# FTDI.net
KiCad netlist of a schematic drawn in Altium Designer
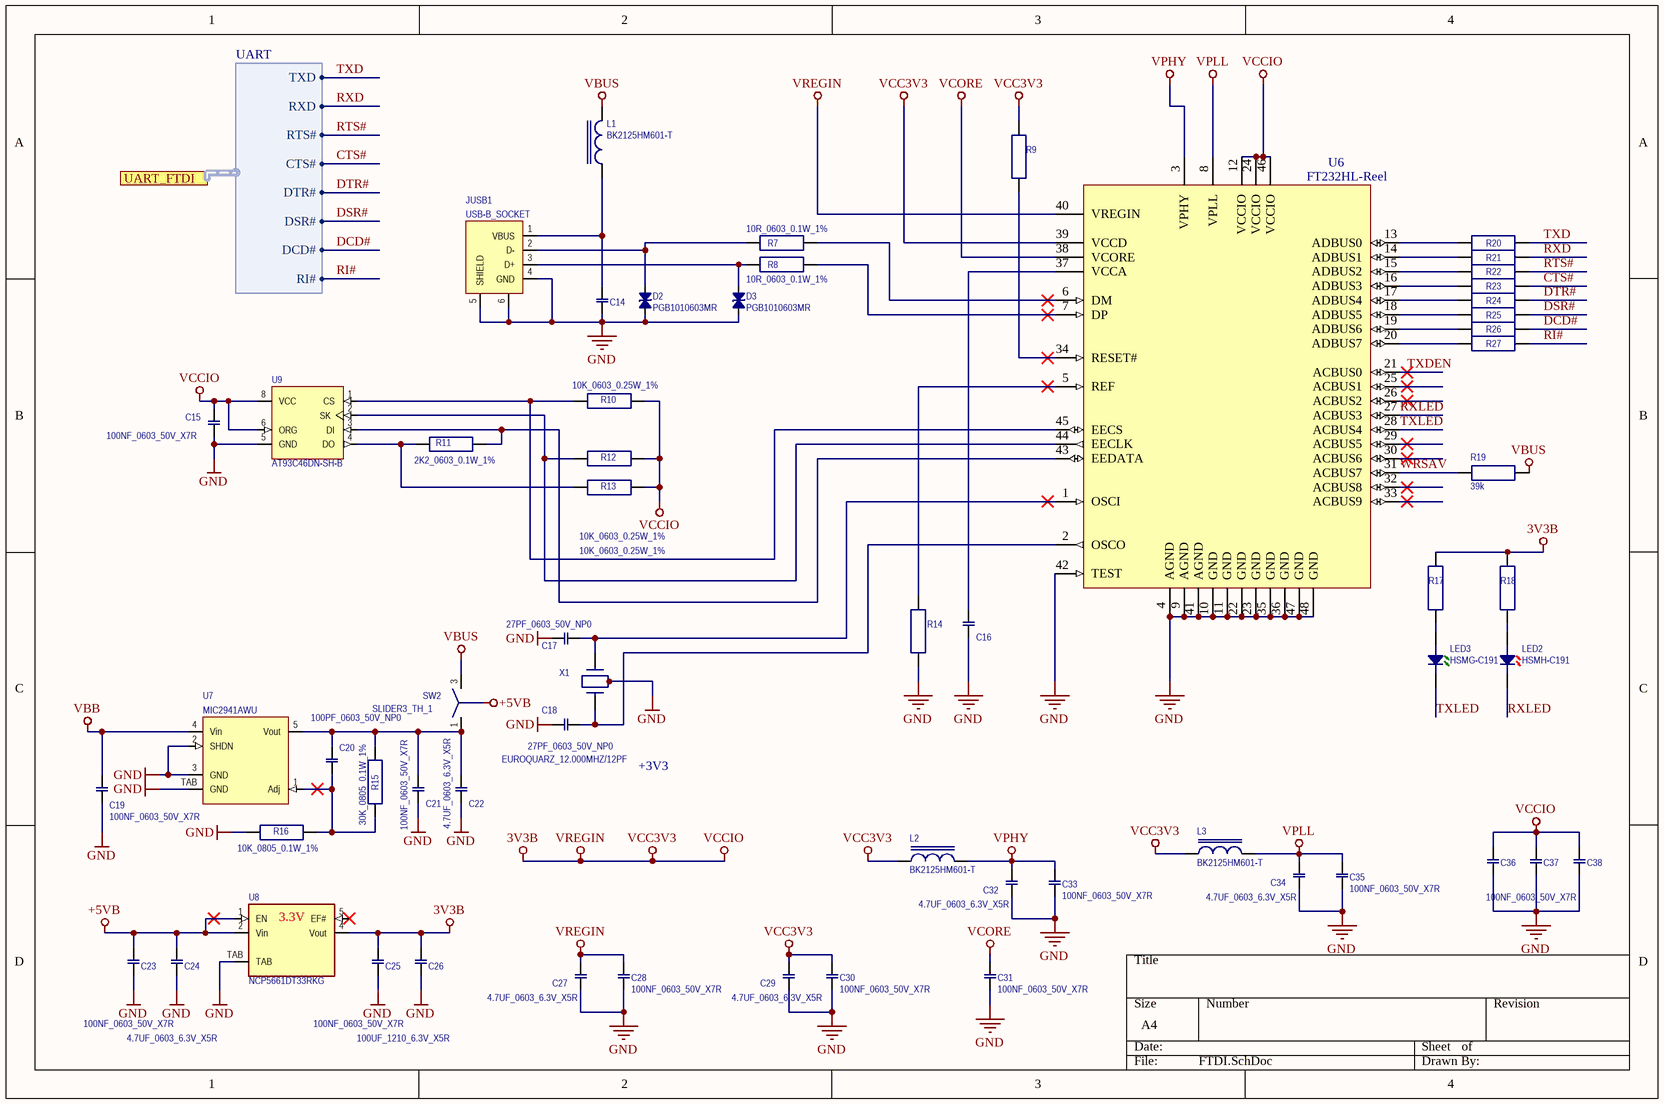
[diagram p0: FTDI.SchDoc]

(export (version "E")
  (design (tool "Eeschema 10.0.6"))
  (components
    (comp (ref "C14")
      (value "10NF_0603_50V_X7R")
      (footprint "CAP0603")
      (description "128-8255    Capacitor MLC-X7R_0603_100NF_10%_50V; C0603C104K5RAC; KEMET; RoHS=Yes")
      (libsource (lib "ONEMULA_V2") (part "100NF_0603_50V_X7R"))
    )
    (comp (ref "C15")
      (value "100NF_0603_50V_X7R")
      (footprint "CAP0603")
      (description "128-8255    Capacitor MLC-X7R_0603_100NF_10%_50V; C0603C104K5RAC; KEMET; RoHS=Yes")
      (libsource (lib "*") (part "100NF_0603_50V_X7R"))
    )
    (comp (ref "C16")
      (value "100NF_0603_50V_X7R")
      (footprint "CAP0603")
      (description "128-8255    Capacitor MLC-X7R_0603_100NF_10%_50V; C0603C104K5RAC; KEMET; RoHS=Yes")
      (libsource (lib "ONEMULA_V2") (part "100NF_0603_50V_X7R"))
    )
    (comp (ref "C17")
      (value "27PF_0603_50V_NP0")
      (footprint "CAP0603")
      (description "141-4627    Capacitor MLC-NPO_0603_27PF_5%_50V; C0603C270J5GAC; KEMET; RoHS=Yes")
      (libsource (lib "*") (part "27PF_0603_50V_NP0"))
    )
    (comp (ref "C18")
      (value "27PF_0603_50V_NP0")
      (footprint "CAP0603")
      (description "141-4627    Capacitor MLC-NPO_0603_27PF_5%_50V; C0603C270J5GAC; KEMET; RoHS=Yes")
      (libsource (lib "*") (part "27PF_0603_50V_NP0"))
    )
    (comp (ref "C19")
      (value "100NF_0603_50V_X7R")
      (footprint "CAP0603")
      (description "128-8255    Capacitor MLC-X7R_0603_100NF_10%_50V; C0603C104K5RAC; KEMET; RoHS=Yes")
      (libsource (lib "*") (part "100NF_0603_50V_X7R"))
    )
    (comp (ref "C20")
      (value "100PF_0603_50V_NP0")
      (footprint "CAP0603")
      (description "141-4603    Capacitor MLC-NPO_0603_100PF_5%_50V; C0603C101J5GAC; KEMET; RoHS=Yes")
      (libsource (lib "*") (part "100PF_0603_50V_NP0"))
    )
    (comp (ref "C21")
      (value "100NF_0603_50V_X7R")
      (footprint "CAP0603")
      (description "128-8255    Capacitor MLC-X7R_0603_100NF_10%_50V; C0603C104K5RAC; KEMET; RoHS=Yes")
      (libsource (lib "*") (part "100NF_0603_50V_X7R"))
    )
    (comp (ref "C22")
      (value "4.7UF_0603_6.3V_X5R")
      (footprint "CAP0603")
      (description "940-2110    Capacitor MLC-X5R_0603_4.7uF_10%_6.3V; 225520613672; PHYCOMP; RoHS=Yes")
      (libsource (lib "*") (part "4.7UF_0603_6.3V_X5R"))
    )
    (comp (ref "C23")
      (value "100NF_0603_50V_X7R")
      (footprint "CAP0603")
      (description "128-8255    Capacitor MLC-X7R_0603_100NF_10%_50V; C0603C104K5RAC; KEMET; RoHS=Yes")
      (libsource (lib "*") (part "100NF_0603_50V_X7R"))
    )
    (comp (ref "C24")
      (value "4.7UF_0603_6.3V_X5R")
      (footprint "CAP0603")
      (description "940-2110    Capacitor MLC-X5R_0603_4.7uF_10%_6.3V; 225520613672; PHYCOMP; RoHS=Yes")
      (libsource (lib "*") (part "4.7UF_0603_6.3V_X5R"))
    )
    (comp (ref "C25")
      (value "100NF_0603_50V_X7R")
      (footprint "CAP0603")
      (description "128-8255    Capacitor MLC-X7R_0603_100NF_10%_50V; C0603C104K5RAC; KEMET; RoHS=Yes")
      (libsource (lib "*") (part "100NF_0603_50V_X7R"))
    )
    (comp (ref "C26")
      (value "100UF_1210_6.3V_X5R")
      (footprint "CAP1210")
      (description "182-8817    Capacitor CML 100uF_1210_6.3V_X5R_20%; GRM32ER60J107ME20L; MURATA; RoHS=Yes")
      (libsource (lib "*") (part "100UF_1210_6.3V_X5R"))
    )
    (comp (ref "C27")
      (value "4.7UF_0603_6.3V_X5R")
      (footprint "CAP0603")
      (description "940-2110    Capacitor MLC-X5R_0603_4.7uF_10%_6.3V; 225520613672; PHYCOMP; RoHS=Yes")
      (libsource (lib "ONEMULA_V2") (part "4.7UF_0603_6.3V_X5R"))
    )
    (comp (ref "C28")
      (value "100NF_0603_50V_X7R")
      (footprint "CAP0603")
      (description "128-8255    Capacitor MLC-X7R_0603_100NF_10%_50V; C0603C104K5RAC; KEMET; RoHS=Yes")
      (libsource (lib "ONEMULA_V2") (part "100NF_0603_50V_X7R"))
    )
    (comp (ref "C29")
      (value "4.7UF_0603_6.3V_X5R")
      (footprint "CAP0603")
      (description "940-2110    Capacitor MLC-X5R_0603_4.7uF_10%_6.3V; 225520613672; PHYCOMP; RoHS=Yes")
      (libsource (lib "ONEMULA_V2") (part "4.7UF_0603_6.3V_X5R"))
    )
    (comp (ref "C30")
      (value "100NF_0603_50V_X7R")
      (footprint "CAP0603")
      (description "128-8255    Capacitor MLC-X7R_0603_100NF_10%_50V; C0603C104K5RAC; KEMET; RoHS=Yes")
      (libsource (lib "ONEMULA_V2") (part "100NF_0603_50V_X7R"))
    )
    (comp (ref "C31")
      (value "100NF_0603_50V_X7R")
      (footprint "CAP0603")
      (description "128-8255    Capacitor MLC-X7R_0603_100NF_10%_50V; C0603C104K5RAC; KEMET; RoHS=Yes")
      (libsource (lib "ONEMULA_V2") (part "100NF_0603_50V_X7R"))
    )
    (comp (ref "C32")
      (value "4.7UF_0603_6.3V_X5R")
      (footprint "CAP0603")
      (description "940-2110    Capacitor MLC-X5R_0603_4.7uF_10%_6.3V; 225520613672; PHYCOMP; RoHS=Yes")
      (libsource (lib "ONEMULA_V2") (part "4.7UF_0603_6.3V_X5R"))
    )
    (comp (ref "C33")
      (value "100NF_0603_50V_X7R")
      (footprint "CAP0603")
      (description "128-8255    Capacitor MLC-X7R_0603_100NF_10%_50V; C0603C104K5RAC; KEMET; RoHS=Yes")
      (libsource (lib "ONEMULA_V2") (part "100NF_0603_50V_X7R"))
    )
    (comp (ref "C34")
      (value "4.7UF_0603_6.3V_X5R")
      (footprint "CAP0603")
      (description "940-2110    Capacitor MLC-X5R_0603_4.7uF_10%_6.3V; 225520613672; PHYCOMP; RoHS=Yes")
      (libsource (lib "ONEMULA_V2") (part "4.7UF_0603_6.3V_X5R"))
    )
    (comp (ref "C35")
      (value "100NF_0603_50V_X7R")
      (footprint "CAP0603")
      (description "128-8255    Capacitor MLC-X7R_0603_100NF_10%_50V; C0603C104K5RAC; KEMET; RoHS=Yes")
      (libsource (lib "ONEMULA_V2") (part "100NF_0603_50V_X7R"))
    )
    (comp (ref "C36")
      (value "100NF_0603_50V_X7R")
      (footprint "CAP0603")
      (description "128-8255    Capacitor MLC-X7R_0603_100NF_10%_50V; C0603C104K5RAC; KEMET; RoHS=Yes")
      (libsource (lib "ONEMULA_V2") (part "100NF_0603_50V_X7R"))
    )
    (comp (ref "C37")
      (value "100NF_0603_50V_X7R")
      (footprint "CAP0603")
      (description "128-8255    Capacitor MLC-X7R_0603_100NF_10%_50V; C0603C104K5RAC; KEMET; RoHS=Yes")
      (libsource (lib "ONEMULA_V2") (part "100NF_0603_50V_X7R"))
    )
    (comp (ref "C38")
      (value "100NF_0603_50V_X7R")
      (footprint "CAP0603")
      (description "128-8255    Capacitor MLC-X7R_0603_100NF_10%_50V; C0603C104K5RAC; KEMET; RoHS=Yes")
      (libsource (lib "ONEMULA_V2") (part "100NF_0603_50V_X7R"))
    )
    (comp (ref "D2")
      (value "PGB1010603MR")
      (footprint "0603")
      (description "175-7240   SUPPRESSOR, ESD, 15KV; PGB1010603MR; LITTELFUSE; RoHS=Yes")
      (libsource (lib "ONEMULA_V2") (part "PGB1010603MR"))
    )
    (comp (ref "D3")
      (value "PGB1010603MR")
      (footprint "0603")
      (description "175-7240   SUPPRESSOR, ESD, 15KV; PGB1010603MR; LITTELFUSE; RoHS=Yes")
      (libsource (lib "ONEMULA_V2") (part "PGB1010603MR"))
    )
    (comp (ref "JUSB1")
      (value "USB-B_SOCKET")
      (footprint "USB-B_SOCKET")
      (description "117-7885    USB PANEL SOCKET PCB TYPE B; 2411 02; LUMBERG; RoHS=Yes")
      (libsource (lib "ONEMULA_V2") (part "USB-B_SOCKET"))
    )
    (comp (ref "L1")
      (value "BK2125HM601-T")
      (footprint "L0805")
      (description "161-1995    FERRITE CHIP BEAD 500mA, 600Ohm@100MHz; BK2125HM601-T; TAIYO YUDEN; RoHS=Yes")
      (libsource (lib "ONEMULA_V2") (part "BK2125HM601-T"))
    )
    (comp (ref "L2")
      (value "BK2125HM601-T")
      (footprint "L0805")
      (description "161-1995    FERRITE CHIP BEAD 500mA, 600Ohm@100MHz; BK2125HM601-T; TAIYO YUDEN; RoHS=Yes")
      (libsource (lib "ONEMULA_V2") (part "BK2125HM601-T"))
    )
    (comp (ref "L3")
      (value "BK2125HM601-T")
      (footprint "L0805")
      (description "161-1995    FERRITE CHIP BEAD 500mA, 600Ohm@100MHz; BK2125HM601-T; TAIYO YUDEN; RoHS=Yes")
      (libsource (lib "ONEMULA_V2") (part "BK2125HM601-T"))
    )
    (comp (ref "LED2")
      (value "HSMH-C191")
      (footprint "D0603")
      (description "855-4650    LED DIODE RED 25mA, 0603; HSMH-C191; AVAGO TECHNOLOGIES; RoHS=Yes")
      (libsource (lib "ONEMULA_V2") (part "HSMH-C191"))
    )
    (comp (ref "LED3")
      (value "HSMG-C191")
      (footprint "D0603")
      (description "855-4617    LED DIODE GREEN 20mA, 0603; HSMG-C191; AVAGO TECHNOLOGIES; RoHS=Yes")
      (libsource (lib "ONEMULA_V2") (part "HSMG-C191"))
    )
    (comp (ref "R7")
      (value "10R_0603_0.1W_1%")
      (footprint "R0603")
      (description "146-9751    RESISTOR MF_0603_10R_0.1W_1%_75V; CRCW060310R0FKEA; VISHAY; RoHS=Yes")
      (libsource (lib "ONEMULA_V2") (part "10R_0603_0.1W_1%"))
    )
    (comp (ref "R8")
      (value "10R_0603_0.1W_1%")
      (footprint "R0603")
      (description "146-9751    RESISTOR MF_0603_10R_0.1W_1%_75V; CRCW060310R0FKEA; VISHAY; RoHS=Yes")
      (libsource (lib "ONEMULA_V2") (part "10R_0603_0.1W_1%"))
    )
    (comp (ref "R9")
      (value "10K_0603_0.25W_1%")
      (footprint "R0603")
      (description "173-8918    RESISTOR MF_0603_10K_0.25W_1%; CRCW06010K0FKEAHP VISHAY; RoHS=Yes")
      (libsource (lib "ONEMULA_V2") (part "10K_0603_0.25W_1%"))
    )
    (comp (ref "R10")
      (value "10K_0603_0.25W_1%")
      (footprint "R0603")
      (description "173-8918    RESISTOR MF_0603_10K_0.25W_1%; CRCW06010K0FKEAHP VISHAY; RoHS=Yes")
      (libsource (lib "*") (part "10K_0603_0.25W_1%"))
    )
    (comp (ref "R11")
      (value "2K2_0603_0.1W_1%")
      (footprint "R0603")
      (description "146-9765    RESISTOR MF_0603_2K2_0.1W_1%_75V; CRCW06032K20FKEA; VISHAY; RoHS=Yes")
      (libsource (lib "*") (part "2K2_0603_0.1W_1%"))
    )
    (comp (ref "R12")
      (value "10K_0603_0.25W_1%")
      (footprint "R0603")
      (description "173-8918    RESISTOR MF_0603_10K_0.25W_1%; CRCW06010K0FKEAHP VISHAY; RoHS=Yes")
      (libsource (lib "*") (part "10K_0603_0.25W_1%"))
    )
    (comp (ref "R13")
      (value "10K_0603_0.25W_1%")
      (footprint "R0603")
      (description "173-8918    RESISTOR MF_0603_10K_0.25W_1%; CRCW06010K0FKEAHP VISHAY; RoHS=Yes")
      (libsource (lib "*") (part "10K_0603_0.25W_1%"))
    )
    (comp (ref "R14")
      (value "12K_0603_0.25W_1%")
      (footprint "R0603")
      (libsource (lib "ONEMULA_V2") (part "12K_0603_0.25W_1%"))
    )
    (comp (ref "R15")
      (value "30K_0805_0.1W_1%")
      (footprint "R0805")
      (libsource (lib "*") (part "30K_0805_0.1W_1%"))
    )
    (comp (ref "R16")
      (value "10K_0805_0.1W_1%")
      (footprint "R0805")
      (libsource (lib "*") (part "10K_0805_0.1W_1%"))
    )
    (comp (ref "R17")
      (value "47R_0603_0.1W_1%")
      (footprint "R0603")
      (description "146-9751    RESISTOR MF_0603_10R_0.1W_1%_75V; CRCW060310R0FKEA; VISHAY; RoHS=Yes")
      (libsource (lib "ONEMULA_V2") (part "10R_0603_0.1W_1%"))
    )
    (comp (ref "R18")
      (value "62R_0603_0.1W_1%")
      (footprint "R0603")
      (description "146-9751    RESISTOR MF_0603_10R_0.1W_1%_75V; CRCW060310R0FKEA; VISHAY; RoHS=Yes")
      (libsource (lib "ONEMULA_V2") (part "10R_0603_0.1W_1%"))
    )
    (comp (ref "R19")
      (value "39k")
      (footprint "R0603")
      (description "923-3130    RESISTOR MF_0603_0.0R_0.1W_50V; RC0603JR-070RL; YAGEO; RoHS=Yes")
      (libsource (lib "ONEMULA_V2") (part "0.0R_0603_0.063W_5%"))
    )
    (comp (ref "R20")
      (value "100R_0603_0.1W_1%")
      (footprint "R0603")
      (description "146-9752    RESISTOR MF_0603_100R_0.1W_1%_75V; CRCW0603100RFKEA; VISHAY; RoHS=Yes")
      (libsource (lib "ONEMULA_V2") (part "100R_0603_0.1W_1%"))
    )
    (comp (ref "R21")
      (value "100R_0603_0.1W_1%")
      (footprint "R0603")
      (description "146-9752    RESISTOR MF_0603_100R_0.1W_1%_75V; CRCW0603100RFKEA; VISHAY; RoHS=Yes")
      (libsource (lib "ONEMULA_V2") (part "100R_0603_0.1W_1%"))
    )
    (comp (ref "R22")
      (value "100R_0603_0.1W_1%")
      (footprint "R0603")
      (description "146-9752    RESISTOR MF_0603_100R_0.1W_1%_75V; CRCW0603100RFKEA; VISHAY; RoHS=Yes")
      (libsource (lib "ONEMULA_V2") (part "100R_0603_0.1W_1%"))
    )
    (comp (ref "R23")
      (value "100R_0603_0.1W_1%")
      (footprint "R0603")
      (description "146-9752    RESISTOR MF_0603_100R_0.1W_1%_75V; CRCW0603100RFKEA; VISHAY; RoHS=Yes")
      (libsource (lib "ONEMULA_V2") (part "100R_0603_0.1W_1%"))
    )
    (comp (ref "R24")
      (value "100R_0603_0.1W_1%")
      (footprint "R0603")
      (description "146-9752    RESISTOR MF_0603_100R_0.1W_1%_75V; CRCW0603100RFKEA; VISHAY; RoHS=Yes")
      (libsource (lib "ONEMULA_V2") (part "100R_0603_0.1W_1%"))
    )
    (comp (ref "R25")
      (value "100R_0603_0.1W_1%")
      (footprint "R0603")
      (description "146-9752    RESISTOR MF_0603_100R_0.1W_1%_75V; CRCW0603100RFKEA; VISHAY; RoHS=Yes")
      (libsource (lib "ONEMULA_V2") (part "100R_0603_0.1W_1%"))
    )
    (comp (ref "R26")
      (value "100R_0603_0.1W_1%")
      (footprint "R0603")
      (description "146-9752    RESISTOR MF_0603_100R_0.1W_1%_75V; CRCW0603100RFKEA; VISHAY; RoHS=Yes")
      (libsource (lib "ONEMULA_V2") (part "100R_0603_0.1W_1%"))
    )
    (comp (ref "R27")
      (value "100R_0603_0.1W_1%")
      (footprint "R0603")
      (description "146-9752    RESISTOR MF_0603_100R_0.1W_1%_75V; CRCW0603100RFKEA; VISHAY; RoHS=Yes")
      (libsource (lib "ONEMULA_V2") (part "100R_0603_0.1W_1%"))
    )
    (comp (ref "SW2")
      (value "SLIDER3_TH_1")
      (footprint "X3APH-SLIDER")
      (description "674-345     SWITCH SLIDE SPDT VERT; 09-03290-01; EAO; RoHS=Yes")
      (libsource (lib "*") (part "SLIDER3_TH_1"))
    )
    (comp (ref "U6")
      (value "FT232HL-Reel")
      (footprint "LQFP-48_N")
      (description "Single Channel Hi-Speed USB to Multipurpose UART/FIFO IC, 48-pin LQFP, Tape and Reel")
      (fields (field (name "MANUFACTURER") "FTDI"))
      (libsource (lib "FTDI FT Series") (part "FT232HL-Reel"))
    )
    (comp (ref "U7")
      (value "MIC2941AWU")
      (footprint "TO263_5")
      (description "155-6739    VOLTAGE REGULATOR, ADJ/1,5A, MIC2941AWU; MICREL; RoHS=Yes")
      (libsource (lib "*") (part "MIC2941AWU"))
    )
    (comp (ref "U8")
      (value "NCP5661DT33RKG")
      (footprint "DPAK5")
      (description "ONSEMI      VOLTAGE REGULATOR NCP5661DT33RKG, LINEAR, LDO, 3.3V/1A, DPAK5; ONSEMI; RoHS=Yes")
      (libsource (lib "ONEMULA_V1_ALLPATCHES") (part "NCP5661DT33RKG"))
    )
    (comp (ref "U9")
      (value "AT93C46DN-SH-B")
      (footprint "SOIC8")
      (description "145-5086    EEPROM 1kBit; AT93C46DN-SH-B; SOIC8; ATMEL; RoHS=Yes")
      (libsource (lib "ONEMULA_V1_ALLPATCHES") (part "AT93C46DN-SH-B"))
    )
    (comp (ref "X1")
      (value "EUROQUARZ_12.000MHZ/12PF")
      (footprint "EUROQUARZ_3.2X5.0MM")
      (description "164-0927    CRYSTAL, SMD, 12.000MHZ MJ/30/30/40/12PF; EUROQUARZ RoHS=Yes")
      (libsource (lib "*") (part "EUROQUARZ_12.000MHZ/12PF"))
    )
  )
  (nets
    (net (code "2") (name "+5VB") (class "Default")
      (node (ref "C23") (pin "1") (pinfunction "1_1") (pintype "passive"))
      (node (ref "C24") (pin "1") (pinfunction "1_1") (pintype "passive"))
      (node (ref "SW2") (pin "2") (pinfunction "2_2") (pintype "passive"))
      (node (ref "U8") (pin "1") (pinfunction "EN_1") (pintype "input"))
      (node (ref "U8") (pin "2") (pinfunction "Vin_2") (pintype "power_in"))
    )
    (net (code "3") (name "/CTS#") (class "Default")
      (node (ref "R23") (pin "2") (pinfunction "2_2") (pintype "passive"))
    )
    (net (code "4") (name "/DCD#") (class "Default")
      (node (ref "R26") (pin "2") (pinfunction "2_2") (pintype "passive"))
    )
    (net (code "5") (name "/DSR#") (class "Default")
      (node (ref "R25") (pin "2") (pinfunction "2_2") (pintype "passive"))
    )
    (net (code "6") (name "/DTR#") (class "Default")
      (node (ref "R24") (pin "2") (pinfunction "2_2") (pintype "passive"))
    )
    (net (code "7") (name "/RI#") (class "Default")
      (node (ref "R27") (pin "2") (pinfunction "2_2") (pintype "passive"))
    )
    (net (code "8") (name "/RTS#") (class "Default")
      (node (ref "R22") (pin "2") (pinfunction "2_2") (pintype "passive"))
    )
    (net (code "9") (name "/RXD") (class "Default")
      (node (ref "R21") (pin "2") (pinfunction "2_2") (pintype "passive"))
    )
    (net (code "10") (name "/RXLED") (class "Default")
      (node (ref "LED2") (pin "K") (pinfunction "K_K") (pintype "passive"))
      (node (ref "U6") (pin "27") (pinfunction "ACBUS3_27") (pintype "bidirectional"))
    )
    (net (code "11") (name "/TXD") (class "Default")
      (node (ref "R20") (pin "2") (pinfunction "2_2") (pintype "passive"))
    )
    (net (code "12") (name "/TXDEN") (class "Default")
      (node (ref "U6") (pin "21") (pinfunction "ACBUS0_21") (pintype "bidirectional"))
    )
    (net (code "13") (name "/TXLED") (class "Default")
      (node (ref "LED3") (pin "K") (pinfunction "K_K") (pintype "passive"))
      (node (ref "U6") (pin "28") (pinfunction "ACBUS4_28") (pintype "bidirectional"))
    )
    (net (code "14") (name "/WRSAV") (class "Default")
      (node (ref "R19") (pin "1") (pinfunction "1_1") (pintype "passive"))
      (node (ref "U6") (pin "31") (pinfunction "ACBUS7_31") (pintype "bidirectional"))
    )
    (net (code "16") (name "3V3B") (class "Default")
      (node (ref "C15") (pin "1") (pinfunction "1_1") (pintype "passive"))
      (node (ref "C25") (pin "1") (pinfunction "1_1") (pintype "passive"))
      (node (ref "C26") (pin "1") (pinfunction "1_1") (pintype "passive"))
      (node (ref "C27") (pin "1") (pinfunction "1_1") (pintype "passive"))
      (node (ref "C28") (pin "1") (pinfunction "1_1") (pintype "passive"))
      (node (ref "C29") (pin "1") (pinfunction "1_1") (pintype "passive"))
      (node (ref "C30") (pin "1") (pinfunction "1_1") (pintype "passive"))
      (node (ref "C36") (pin "1") (pinfunction "1_1") (pintype "passive"))
      (node (ref "C37") (pin "1") (pinfunction "1_1") (pintype "passive"))
      (node (ref "C38") (pin "1") (pinfunction "1_1") (pintype "passive"))
      (node (ref "L2") (pin "1") (pinfunction "1_1") (pintype "passive"))
      (node (ref "L3") (pin "1") (pinfunction "1_1") (pintype "passive"))
      (node (ref "R10") (pin "2") (pinfunction "2_2") (pintype "passive"))
      (node (ref "R12") (pin "2") (pinfunction "2_2") (pintype "passive"))
      (node (ref "R13") (pin "2") (pinfunction "2_2") (pintype "passive"))
      (node (ref "R17") (pin "2") (pinfunction "2_2") (pintype "passive"))
      (node (ref "R18") (pin "2") (pinfunction "2_2") (pintype "passive"))
      (node (ref "R9") (pin "2") (pinfunction "2_2") (pintype "passive"))
      (node (ref "U6") (pin "12") (pinfunction "VCCIO_12") (pintype "power_in"))
      (node (ref "U6") (pin "24") (pinfunction "VCCIO_24") (pintype "power_in"))
      (node (ref "U6") (pin "39") (pinfunction "VCCD_39") (pintype "power_in"))
      (node (ref "U6") (pin "40") (pinfunction "VREGIN_40") (pintype "power_in"))
      (node (ref "U6") (pin "46") (pinfunction "VCCIO_46") (pintype "power_in"))
      (node (ref "U8") (pin "4") (pinfunction "Vout_4") (pintype "power_in"))
      (node (ref "U9") (pin "6") (pinfunction "ORG_6") (pintype "input"))
      (node (ref "U9") (pin "8") (pinfunction "VCC_8") (pintype "power_in"))
    )
    (net (code "17") (name "GND") (class "Default")
      (node (ref "C14") (pin "2") (pinfunction "2_2") (pintype "passive"))
      (node (ref "C15") (pin "2") (pinfunction "2_2") (pintype "passive"))
      (node (ref "C16") (pin "2") (pinfunction "2_2") (pintype "passive"))
      (node (ref "C17") (pin "2") (pinfunction "2_2") (pintype "passive"))
      (node (ref "C18") (pin "2") (pinfunction "2_2") (pintype "passive"))
      (node (ref "C19") (pin "1") (pinfunction "1_1") (pintype "passive"))
      (node (ref "C21") (pin "2") (pinfunction "2_2") (pintype "passive"))
      (node (ref "C22") (pin "2") (pinfunction "2_2") (pintype "passive"))
      (node (ref "C23") (pin "2") (pinfunction "2_2") (pintype "passive"))
      (node (ref "C24") (pin "2") (pinfunction "2_2") (pintype "passive"))
      (node (ref "C25") (pin "2") (pinfunction "2_2") (pintype "passive"))
      (node (ref "C26") (pin "2") (pinfunction "2_2") (pintype "passive"))
      (node (ref "C27") (pin "2") (pinfunction "2_2") (pintype "passive"))
      (node (ref "C28") (pin "2") (pinfunction "2_2") (pintype "passive"))
      (node (ref "C29") (pin "2") (pinfunction "2_2") (pintype "passive"))
      (node (ref "C30") (pin "2") (pinfunction "2_2") (pintype "passive"))
      (node (ref "C31") (pin "2") (pinfunction "2_2") (pintype "passive"))
      (node (ref "C32") (pin "2") (pinfunction "2_2") (pintype "passive"))
      (node (ref "C33") (pin "2") (pinfunction "2_2") (pintype "passive"))
      (node (ref "C34") (pin "2") (pinfunction "2_2") (pintype "passive"))
      (node (ref "C35") (pin "2") (pinfunction "2_2") (pintype "passive"))
      (node (ref "C36") (pin "2") (pinfunction "2_2") (pintype "passive"))
      (node (ref "C37") (pin "2") (pinfunction "2_2") (pintype "passive"))
      (node (ref "C38") (pin "2") (pinfunction "2_2") (pintype "passive"))
      (node (ref "D2") (pin "1") (pinfunction "1_1") (pintype "passive"))
      (node (ref "D3") (pin "1") (pinfunction "1_1") (pintype "passive"))
      (node (ref "JUSB1") (pin "4") (pinfunction "GND_4") (pintype "power_in"))
      (node (ref "JUSB1") (pin "5") (pinfunction "SHIELD_5") (pintype "passive"))
      (node (ref "JUSB1") (pin "6") (pinfunction "SHIELD_6") (pintype "passive"))
      (node (ref "R14") (pin "1") (pinfunction "1_1") (pintype "passive"))
      (node (ref "R16") (pin "1") (pinfunction "1_1") (pintype "passive"))
      (node (ref "U6") (pin "10") (pinfunction "GND_10") (pintype "power_in"))
      (node (ref "U6") (pin "11") (pinfunction "GND_11") (pintype "power_in"))
      (node (ref "U6") (pin "22") (pinfunction "GND_22") (pintype "power_in"))
      (node (ref "U6") (pin "23") (pinfunction "GND_23") (pintype "power_in"))
      (node (ref "U6") (pin "35") (pinfunction "GND_35") (pintype "power_in"))
      (node (ref "U6") (pin "36") (pinfunction "GND_36") (pintype "power_in"))
      (node (ref "U6") (pin "4") (pinfunction "AGND_4") (pintype "power_in"))
      (node (ref "U6") (pin "41") (pinfunction "AGND_41") (pintype "power_in"))
      (node (ref "U6") (pin "42") (pinfunction "TEST_42") (pintype "input"))
      (node (ref "U6") (pin "47") (pinfunction "GND_47") (pintype "power_in"))
      (node (ref "U6") (pin "48") (pinfunction "GND_48") (pintype "power_in"))
      (node (ref "U6") (pin "9") (pinfunction "AGND_9") (pintype "power_in"))
      (node (ref "U7") (pin "2") (pinfunction "SHDN_2") (pintype "input"))
      (node (ref "U7") (pin "3") (pinfunction "GND_3") (pintype "power_in"))
      (node (ref "U7") (pin "TAB") (pinfunction "GND_TAB") (pintype "power_in"))
      (node (ref "U8") (pin "TAB") (pinfunction "TAB_TAB") (pintype "passive"))
      (node (ref "U9") (pin "5") (pinfunction "GND_5") (pintype "power_in"))
      (node (ref "X1") (pin "2") (pinfunction "2_2") (pintype "passive"))
      (node (ref "X1") (pin "4") (pinfunction "4_4") (pintype "passive"))
    )
    (net (code "18") (name "Net-(JUSB1-D+)") (class "Default")
      (node (ref "D3") (pin "2") (pinfunction "2_2") (pintype "passive"))
      (node (ref "JUSB1") (pin "3") (pinfunction "D+_3") (pintype "bidirectional"))
      (node (ref "R8") (pin "1") (pinfunction "1_1") (pintype "passive"))
    )
    (net (code "19") (name "Net-(JUSB1-D-)") (class "Default")
      (node (ref "D2") (pin "2") (pinfunction "2_2") (pintype "passive"))
      (node (ref "JUSB1") (pin "2") (pinfunction "D-_2") (pintype "bidirectional"))
      (node (ref "R7") (pin "1") (pinfunction "1_1") (pintype "passive"))
    )
    (net (code "20") (name "Net-(JUSB1-VBUS)") (class "Default")
      (node (ref "C14") (pin "1") (pinfunction "1_1") (pintype "passive"))
      (node (ref "JUSB1") (pin "1") (pinfunction "VBUS_1") (pintype "power_in"))
      (node (ref "L1") (pin "1") (pinfunction "1_1") (pintype "passive"))
    )
    (net (code "21") (name "Net-(LED2-PadA)") (class "Default")
      (node (ref "LED2") (pin "A") (pinfunction "A_A") (pintype "passive"))
      (node (ref "R18") (pin "1") (pinfunction "1_1") (pintype "passive"))
    )
    (net (code "22") (name "Net-(LED3-PadA)") (class "Default")
      (node (ref "LED3") (pin "A") (pinfunction "A_A") (pintype "passive"))
      (node (ref "R17") (pin "1") (pinfunction "1_1") (pintype "passive"))
    )
    (net (code "23") (name "Net-(U6-ADBUS0)") (class "Default")
      (node (ref "R20") (pin "1") (pinfunction "1_1") (pintype "passive"))
      (node (ref "U6") (pin "13") (pinfunction "ADBUS0_13") (pintype "bidirectional"))
    )
    (net (code "24") (name "Net-(U6-ADBUS1)") (class "Default")
      (node (ref "R21") (pin "1") (pinfunction "1_1") (pintype "passive"))
      (node (ref "U6") (pin "14") (pinfunction "ADBUS1_14") (pintype "bidirectional"))
    )
    (net (code "25") (name "Net-(U6-ADBUS2)") (class "Default")
      (node (ref "R22") (pin "1") (pinfunction "1_1") (pintype "passive"))
      (node (ref "U6") (pin "15") (pinfunction "ADBUS2_15") (pintype "bidirectional"))
    )
    (net (code "26") (name "Net-(U6-ADBUS3)") (class "Default")
      (node (ref "R23") (pin "1") (pinfunction "1_1") (pintype "passive"))
      (node (ref "U6") (pin "16") (pinfunction "ADBUS3_16") (pintype "bidirectional"))
    )
    (net (code "27") (name "Net-(U6-ADBUS4)") (class "Default")
      (node (ref "R24") (pin "1") (pinfunction "1_1") (pintype "passive"))
      (node (ref "U6") (pin "17") (pinfunction "ADBUS4_17") (pintype "bidirectional"))
    )
    (net (code "28") (name "Net-(U6-ADBUS5)") (class "Default")
      (node (ref "R25") (pin "1") (pinfunction "1_1") (pintype "passive"))
      (node (ref "U6") (pin "18") (pinfunction "ADBUS5_18") (pintype "bidirectional"))
    )
    (net (code "29") (name "Net-(U6-ADBUS6)") (class "Default")
      (node (ref "R26") (pin "1") (pinfunction "1_1") (pintype "passive"))
      (node (ref "U6") (pin "19") (pinfunction "ADBUS6_19") (pintype "bidirectional"))
    )
    (net (code "30") (name "Net-(U6-ADBUS7)") (class "Default")
      (node (ref "R27") (pin "1") (pinfunction "1_1") (pintype "passive"))
      (node (ref "U6") (pin "20") (pinfunction "ADBUS7_20") (pintype "bidirectional"))
    )
    (net (code "31") (name "Net-(U6-DM)") (class "Default")
      (node (ref "R7") (pin "2") (pinfunction "2_2") (pintype "passive"))
      (node (ref "U6") (pin "6") (pinfunction "DM_6") (pintype "input"))
    )
    (net (code "32") (name "Net-(U6-DP)") (class "Default")
      (node (ref "R8") (pin "2") (pinfunction "2_2") (pintype "passive"))
      (node (ref "U6") (pin "7") (pinfunction "DP_7") (pintype "input"))
    )
    (net (code "33") (name "Net-(U6-EECLK)") (class "Default")
      (node (ref "R12") (pin "1") (pinfunction "1_1") (pintype "passive"))
      (node (ref "U6") (pin "44") (pinfunction "EECLK_44") (pintype "output"))
      (node (ref "U9") (pin "2") (pinfunction "SK_2") (pintype "input"))
    )
    (net (code "34") (name "Net-(U6-EECS)") (class "Default")
      (node (ref "R10") (pin "1") (pinfunction "1_1") (pintype "passive"))
      (node (ref "U6") (pin "45") (pinfunction "EECS_45") (pintype "bidirectional"))
      (node (ref "U9") (pin "1") (pinfunction "CS_1") (pintype "input"))
    )
    (net (code "35") (name "Net-(U6-EEDATA)") (class "Default")
      (node (ref "R11") (pin "2") (pinfunction "2_2") (pintype "passive"))
      (node (ref "U6") (pin "43") (pinfunction "EEDATA_43") (pintype "bidirectional"))
      (node (ref "U9") (pin "3") (pinfunction "DI_3") (pintype "input"))
    )
    (net (code "36") (name "Net-(U6-OSCI)") (class "Default")
      (node (ref "C17") (pin "1") (pinfunction "1_1") (pintype "passive"))
      (node (ref "U6") (pin "1") (pinfunction "OSCI_1") (pintype "input"))
      (node (ref "X1") (pin "3") (pinfunction "3_3") (pintype "passive"))
    )
    (net (code "37") (name "Net-(U6-OSCO)") (class "Default")
      (node (ref "C18") (pin "1") (pinfunction "1_1") (pintype "passive"))
      (node (ref "U6") (pin "2") (pinfunction "OSCO_2") (pintype "output"))
      (node (ref "X1") (pin "1") (pinfunction "1_1") (pintype "passive"))
    )
    (net (code "38") (name "Net-(U6-REF)") (class "Default")
      (node (ref "R14") (pin "2") (pinfunction "2_2") (pintype "passive"))
      (node (ref "U6") (pin "5") (pinfunction "REF_5") (pintype "input"))
    )
    (net (code "39") (name "Net-(U6-RESET#)") (class "Default")
      (node (ref "R9") (pin "1") (pinfunction "1_1") (pintype "passive"))
      (node (ref "U6") (pin "34") (pinfunction "RESET#_34") (pintype "input"))
    )
    (net (code "40") (name "Net-(U6-VCCA)") (class "Default")
      (node (ref "C16") (pin "1") (pinfunction "1_1") (pintype "passive"))
      (node (ref "U6") (pin "37") (pinfunction "VCCA_37") (pintype "power_in"))
    )
    (net (code "41") (name "Net-(U7-Adj)") (class "Default")
      (node (ref "C20") (pin "1") (pinfunction "1_1") (pintype "passive"))
      (node (ref "R15") (pin "2") (pinfunction "2_2") (pintype "passive"))
      (node (ref "R16") (pin "2") (pinfunction "2_2") (pintype "passive"))
      (node (ref "U7") (pin "1") (pinfunction "Adj_1") (pintype "input"))
    )
    (net (code "42") (name "Net-(U7-Vout)") (class "Default")
      (node (ref "C20") (pin "2") (pinfunction "2_2") (pintype "passive"))
      (node (ref "C21") (pin "1") (pinfunction "1_1") (pintype "passive"))
      (node (ref "C22") (pin "1") (pinfunction "1_1") (pintype "passive"))
      (node (ref "R15") (pin "1") (pinfunction "1_1") (pintype "passive"))
      (node (ref "SW2") (pin "1") (pinfunction "1_1") (pintype "passive"))
      (node (ref "U7") (pin "5") (pinfunction "Vout_5") (pintype "power_in"))
    )
    (net (code "43") (name "Net-(U9-DO)") (class "Default")
      (node (ref "R11") (pin "1") (pinfunction "1_1") (pintype "passive"))
      (node (ref "R13") (pin "1") (pinfunction "1_1") (pintype "passive"))
      (node (ref "U9") (pin "4") (pinfunction "DO_4") (pintype "output"))
    )
    (net (code "44") (name "VBB") (class "Default")
      (node (ref "C19") (pin "2") (pinfunction "2_2") (pintype "passive"))
      (node (ref "U7") (pin "4") (pinfunction "Vin_4") (pintype "power_in"))
    )
    (net (code "45") (name "VBUS") (class "Default")
      (node (ref "L1") (pin "2") (pinfunction "2_2") (pintype "passive"))
      (node (ref "R19") (pin "2") (pinfunction "2_2") (pintype "passive"))
      (node (ref "SW2") (pin "3") (pinfunction "3_3") (pintype "passive"))
    )
    (net (code "46") (name "VCORE") (class "Default")
      (node (ref "C31") (pin "1") (pinfunction "1_1") (pintype "passive"))
      (node (ref "U6") (pin "38") (pinfunction "VCORE_38") (pintype "power_in"))
    )
    (net (code "47") (name "VPHY") (class "Default")
      (node (ref "C32") (pin "1") (pinfunction "1_1") (pintype "passive"))
      (node (ref "C33") (pin "1") (pinfunction "1_1") (pintype "passive"))
      (node (ref "L2") (pin "2") (pinfunction "2_2") (pintype "passive"))
      (node (ref "U6") (pin "3") (pinfunction "VPHY_3") (pintype "power_in"))
    )
    (net (code "48") (name "VPLL") (class "Default")
      (node (ref "C34") (pin "1") (pinfunction "1_1") (pintype "passive"))
      (node (ref "C35") (pin "1") (pinfunction "1_1") (pintype "passive"))
      (node (ref "L3") (pin "2") (pinfunction "2_2") (pintype "passive"))
      (node (ref "U6") (pin "8") (pinfunction "VPLL_8") (pintype "power_in"))
    )
    (net (code "49") (name "unconnected-(U6-ACBUS1-Pad25)") (class "Default")
      (node (ref "U6") (pin "25") (pinfunction "ACBUS1_25") (pintype "bidirectional"))
    )
    (net (code "50") (name "unconnected-(U6-ACBUS2-Pad26)") (class "Default")
      (node (ref "U6") (pin "26") (pinfunction "ACBUS2_26") (pintype "bidirectional"))
    )
    (net (code "51") (name "unconnected-(U6-ACBUS5-Pad29)") (class "Default")
      (node (ref "U6") (pin "29") (pinfunction "ACBUS5_29") (pintype "bidirectional"))
    )
    (net (code "52") (name "unconnected-(U6-ACBUS6-Pad30)") (class "Default")
      (node (ref "U6") (pin "30") (pinfunction "ACBUS6_30") (pintype "bidirectional"))
    )
    (net (code "53") (name "unconnected-(U6-ACBUS8-Pad32)") (class "Default")
      (node (ref "U6") (pin "32") (pinfunction "ACBUS8_32") (pintype "bidirectional"))
    )
    (net (code "54") (name "unconnected-(U6-ACBUS9-Pad33)") (class "Default")
      (node (ref "U6") (pin "33") (pinfunction "ACBUS9_33") (pintype "bidirectional"))
    )
    (net (code "55") (name "unconnected-(U8-EF#-Pad5)") (class "Default")
      (node (ref "U8") (pin "5") (pinfunction "EF#_5") (pintype "input+no_connect"))
    )
  )
)
